# ZX_UNO_0_14.net
KiCad netlist of a schematic drawn in Altium Designer
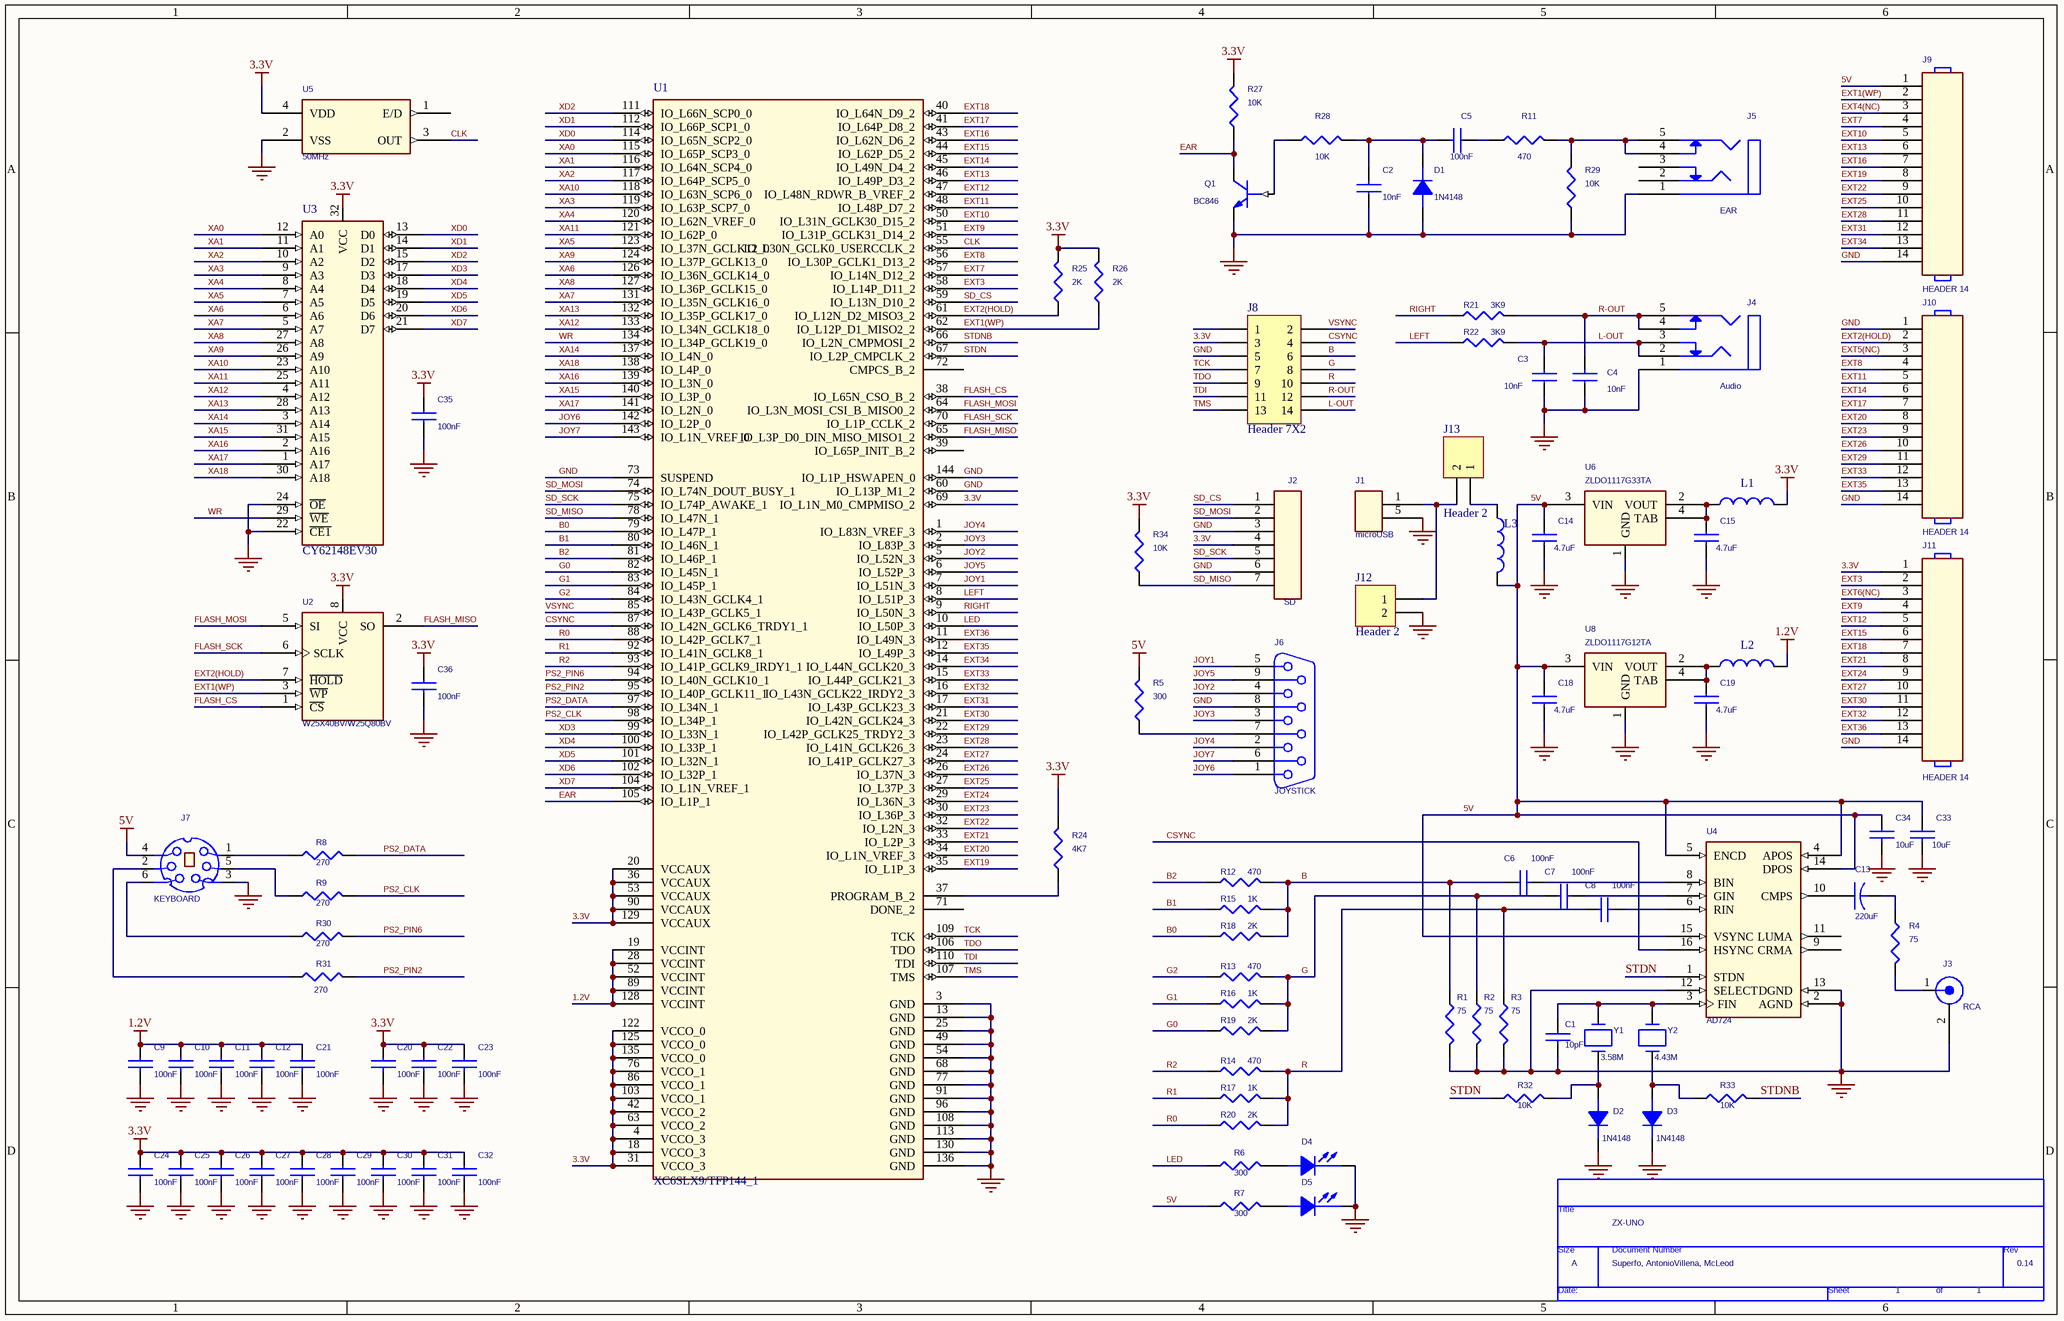
[diagram p0: ZX_UNO_0_14.SchDoc]

(export (version "E")
  (design (tool "Eeschema 10.0.6"))
  (components
    (comp (ref "*")
      (value "TitleBlock0")
      (fields
        (field (name "PAGE COUNT") "1")
        (field (name "PAGE NUMBER") "1")
        (field (name "PAGE SIZE") "A")
        (field (name "TITLE") "ZX-UNO")
        (field (name "REVCODE") "0.14")
        (field (name "DOC") "Superfo, AntonioVillena, McLeod")
      )
      (libsource (lib "*") (part "TitleBlock0"))
    )
    (comp (ref "C1") (value "10pF") (libsource (lib "*") (part "CAP NP_Dup1")))
    (comp (ref "C2") (value "10nF") (libsource (lib "*") (part "CAP NP_Dup1")))
    (comp (ref "C3") (value "10nF") (libsource (lib "*") (part "CAP NP_Dup1")))
    (comp (ref "C4") (value "10nF") (libsource (lib "*") (part "CAP NP_Dup1")))
    (comp (ref "C5") (value "100nF") (libsource (lib "*") (part "CAP NP_Dup1")))
    (comp (ref "C6") (value "100nF") (libsource (lib "*") (part "CAP NP_Dup1")))
    (comp (ref "C7") (value "100nF") (libsource (lib "*") (part "CAP NP_Dup1")))
    (comp (ref "C8") (value "100nF") (libsource (lib "*") (part "CAP NP_Dup1")))
    (comp (ref "C9") (value "100nF") (libsource (lib "*") (part "CAP NP")))
    (comp (ref "C10") (value "100nF") (libsource (lib "*") (part "CAP NP")))
    (comp (ref "C11") (value "100nF") (libsource (lib "*") (part "CAP NP")))
    (comp (ref "C12") (value "100nF") (libsource (lib "*") (part "CAP NP")))
    (comp (ref "C13") (value "220uF") (libsource (lib "*") (part "CAP")))
    (comp (ref "C14") (value "4.7uF") (libsource (lib "*") (part "CAP NP")))
    (comp (ref "C15") (value "4.7uF") (libsource (lib "*") (part "CAP NP")))
    (comp (ref "C18") (value "4.7uF") (libsource (lib "*") (part "CAP NP")))
    (comp (ref "C19") (value "4.7uF") (libsource (lib "*") (part "CAP NP")))
    (comp (ref "C20") (value "100nF") (libsource (lib "*") (part "CAP NP")))
    (comp (ref "C21") (value "100nF") (libsource (lib "*") (part "CAP NP")))
    (comp (ref "C22") (value "100nF") (libsource (lib "*") (part "CAP NP")))
    (comp (ref "C23") (value "100nF") (libsource (lib "*") (part "CAP NP")))
    (comp (ref "C24") (value "100nF") (libsource (lib "*") (part "CAP NP")))
    (comp (ref "C25") (value "100nF") (libsource (lib "*") (part "CAP NP")))
    (comp (ref "C26") (value "100nF") (libsource (lib "*") (part "CAP NP")))
    (comp (ref "C27") (value "100nF") (libsource (lib "*") (part "CAP NP")))
    (comp (ref "C28") (value "100nF") (libsource (lib "*") (part "CAP NP")))
    (comp (ref "C29") (value "100nF") (libsource (lib "*") (part "CAP NP")))
    (comp (ref "C30") (value "100nF") (libsource (lib "*") (part "CAP NP")))
    (comp (ref "C31") (value "100nF") (libsource (lib "*") (part "CAP NP")))
    (comp (ref "C32") (value "100nF") (libsource (lib "*") (part "CAP NP")))
    (comp (ref "C33") (value "10uF") (libsource (lib "*") (part "CAP NP")))
    (comp (ref "C34") (value "10uF") (libsource (lib "*") (part "CAP NP")))
    (comp (ref "C35") (value "100nF") (libsource (lib "*") (part "CAP NP")))
    (comp (ref "C36") (value "100nF") (libsource (lib "*") (part "CAP NP")))
    (comp (ref "D1") (value "1N4148") (libsource (lib "*") (part "DIODE")))
    (comp (ref "D2") (value "1N4148") (libsource (lib "*") (part "DIODE")))
    (comp (ref "D3") (value "1N4148") (libsource (lib "*") (part "DIODE")))
    (comp (ref "D4") (value "LED") (libsource (lib "*") (part "LED")))
    (comp (ref "D5") (value "LED") (libsource (lib "*") (part "LED")))
    (comp (ref "J1") (value "microUSB") (libsource (lib "*") (part "CON2_0")))
    (comp (ref "J2") (value "SD") (libsource (lib "*") (part "CON7")))
    (comp (ref "J3") (value "RCA") (libsource (lib "*") (part "RCA JACK")))
    (comp (ref "J4")
      (value "Audio")
      (footprint "AUDIO JACK STX-3120")
      (libsource (lib "*") (part "PHONEJACK STEREO SW_0"))
    )
    (comp (ref "J5") (value "EAR") (libsource (lib "*") (part "PHONEJACK STEREO SW_0")))
    (comp (ref "J6") (value "JOYSTICK") (libsource (lib "*") (part "CONNECTOR DB9")))
    (comp (ref "J7") (value "KEYBOARD") (libsource (lib "*") (part "M-DIN_0")))
    (comp (ref "J8")
      (value "Header 7X2")
      (footprint "HDR2X7")
      (description "Header, 7-Pin, Dual row")
      (fields (field (name "PUBLISHER") "Altium Limited"))
      (libsource (lib "Miscellaneous Connectors") (part "Header 7X2"))
    )
    (comp (ref "J9") (value "HEADER 14") (libsource (lib "*") (part "HEADER 14")))
    (comp (ref "J10") (value "HEADER 14") (libsource (lib "*") (part "HEADER 14")))
    (comp (ref "J11") (value "HEADER 14") (libsource (lib "*") (part "HEADER 14")))
    (comp (ref "J12")
      (value "Header 2")
      (footprint "HDR1X2")
      (description "Header, 2-Pin")
      (fields (field (name "PUBLISHER") "Altium Limited"))
      (libsource (lib "") (part "Header 2_1"))
    )
    (comp (ref "J13")
      (value "Header 2")
      (footprint "HDR1X2")
      (description "Header, 2-Pin")
      (fields (field (name "PUBLISHER") "Altium Limited"))
      (libsource (lib "Miscellaneous Connectors") (part "Header 2"))
    )
    (comp (ref "L1")
      (value "Inductor")
      (footprint "SM/L_0805")
      (fields (field (name "PUBLISHER") "Altium Limited"))
      (libsource (lib "Miscellaneous Devices") (part "Inductor"))
    )
    (comp (ref "L2")
      (value "Inductor")
      (footprint "SM/L_0805")
      (fields (field (name "PUBLISHER") "Altium Limited"))
      (libsource (lib "Miscellaneous Devices") (part "Inductor"))
    )
    (comp (ref "L3")
      (value "Inductor")
      (footprint "SM/L_0805")
      (fields (field (name "PUBLISHER") "Altium Limited"))
      (libsource (lib "Miscellaneous Devices") (part "Inductor"))
    )
    (comp (ref "Q1") (value "BC846") (libsource (lib "*") (part "BC547")))
    (comp (ref "R1") (value "75") (libsource (lib "*") (part "R")))
    (comp (ref "R2") (value "75") (libsource (lib "*") (part "R")))
    (comp (ref "R3") (value "75") (libsource (lib "*") (part "R")))
    (comp (ref "R4") (value "75") (libsource (lib "*") (part "R")))
    (comp (ref "R5") (value "300") (libsource (lib "*") (part "R")))
    (comp (ref "R6") (value "300") (libsource (lib "*") (part "R")))
    (comp (ref "R7") (value "300") (libsource (lib "*") (part "R")))
    (comp (ref "R8") (value "270") (libsource (lib "*") (part "R")))
    (comp (ref "R9") (value "270") (libsource (lib "*") (part "R")))
    (comp (ref "R11") (value "470") (libsource (lib "*") (part "R")))
    (comp (ref "R12") (value "470") (libsource (lib "*") (part "R")))
    (comp (ref "R13") (value "470") (libsource (lib "*") (part "R")))
    (comp (ref "R14") (value "470") (libsource (lib "*") (part "R")))
    (comp (ref "R15") (value "1K") (libsource (lib "*") (part "R")))
    (comp (ref "R16") (value "1K") (libsource (lib "*") (part "R")))
    (comp (ref "R17") (value "1K") (libsource (lib "*") (part "R")))
    (comp (ref "R18") (value "2K") (libsource (lib "*") (part "R")))
    (comp (ref "R19") (value "2K") (libsource (lib "*") (part "R")))
    (comp (ref "R20") (value "2K") (libsource (lib "*") (part "R")))
    (comp (ref "R21") (value "3K9") (libsource (lib "*") (part "R")))
    (comp (ref "R22") (value "3K9") (libsource (lib "*") (part "R")))
    (comp (ref "R24") (value "4K7") (libsource (lib "*") (part "R")))
    (comp (ref "R25") (value "2K") (libsource (lib "*") (part "R")))
    (comp (ref "R26") (value "2K") (libsource (lib "*") (part "R")))
    (comp (ref "R27") (value "10K") (libsource (lib "*") (part "R")))
    (comp (ref "R28") (value "10K") (libsource (lib "*") (part "R")))
    (comp (ref "R29") (value "10K") (libsource (lib "*") (part "R")))
    (comp (ref "R30") (value "270") (libsource (lib "*") (part "R")))
    (comp (ref "R31") (value "270") (libsource (lib "*") (part "R")))
    (comp (ref "R32") (value "10K") (libsource (lib "*") (part "R")))
    (comp (ref "R33") (value "10K") (libsource (lib "*") (part "R")))
    (comp (ref "R34") (value "10K") (libsource (lib "*") (part "R")))
    (comp (ref "U1")
      (value "XC6SLX9/TFP144_1")
      (libsource (lib "ZX_UNO_0_13_Library") (part "XC6SLX9/TFP144_1"))
    )
    (comp (ref "U2") (value "W25X40BV/W25Q80BV") (libsource (lib "*") (part "AT45DB011/SOIC_3")))
    (comp (ref "U3") (value "CY62148EV30") (libsource (lib "ZX_UNO_0_13_Library") (part "CY62128/SOIC_3")))
    (comp (ref "U4") (value "AD724") (libsource (lib "*") (part "AD724")))
    (comp (ref "U5") (value "50MHz") (libsource (lib "*") (part "CS-403/TO_0")))
    (comp (ref "U6")
      (value "ZLDO1117G33TA")
      (footprint "SM/SOT223")
      (libsource (lib "*") (part "REGULATOR-1_0"))
    )
    (comp (ref "U8")
      (value "ZLDO1117G12TA")
      (footprint "SM/SOT223")
      (libsource (lib "*") (part "REGULATOR-1_0"))
    )
    (comp (ref "Y1") (value "3.58M") (libsource (lib "*") (part "CRYSTAL")))
    (comp (ref "Y2") (value "4.43M") (libsource (lib "*") (part "CRYSTAL")))
  )
  (nets
    (net (code "1") (name "/B") (class "Default")
      (node (ref "C6") (pin "1") (pinfunction "1_1") (pintype "passive"))
      (node (ref "J8") (pin "6") (pinfunction "6_6") (pintype "passive"))
      (node (ref "R1") (pin "1") (pinfunction "1_1") (pintype "passive"))
      (node (ref "R12") (pin "2") (pinfunction "2_2") (pintype "passive"))
      (node (ref "R15") (pin "2") (pinfunction "2_2") (pintype "passive"))
      (node (ref "R18") (pin "2") (pinfunction "2_2") (pintype "passive"))
    )
    (net (code "2") (name "/B0") (class "Default")
      (node (ref "R18") (pin "1") (pinfunction "1_1") (pintype "passive"))
      (node (ref "U1") (pin "79") (pinfunction "IO_L47P_1_79") (pintype "bidirectional"))
    )
    (net (code "3") (name "/B1") (class "Default")
      (node (ref "R15") (pin "1") (pinfunction "1_1") (pintype "passive"))
      (node (ref "U1") (pin "80") (pinfunction "IO_L46N_1_80") (pintype "bidirectional"))
    )
    (net (code "4") (name "/B2") (class "Default")
      (node (ref "R12") (pin "1") (pinfunction "1_1") (pintype "passive"))
      (node (ref "U1") (pin "81") (pinfunction "IO_L46P_1_81") (pintype "bidirectional"))
    )
    (net (code "5") (name "/CLK") (class "Default")
      (node (ref "U1") (pin "55") (pinfunction "IO_L30N_GCLK0_USERCCLK_2_55") (pintype "bidirectional"))
      (node (ref "U5") (pin "3") (pinfunction "OUT_3") (pintype "output"))
    )
    (net (code "6") (name "/CSYNC") (class "Default")
      (node (ref "J8") (pin "4") (pinfunction "4_4") (pintype "passive"))
      (node (ref "U1") (pin "87") (pinfunction "IO_L42N_GCLK6_TRDY1_1_87") (pintype "bidirectional"))
      (node (ref "U4") (pin "16") (pinfunction "HSYNC_16") (pintype "input"))
    )
    (net (code "7") (name "/EAR") (class "Default")
      (node (ref "Q1") (pin "1") (pinfunction "COLLECTOR_1") (pintype "passive"))
      (node (ref "R27") (pin "2") (pinfunction "2_2") (pintype "passive"))
      (node (ref "U1") (pin "105") (pinfunction "IO_L1P_1_105") (pintype "bidirectional"))
    )
    (net (code "8") (name "/EXT1(WP)") (class "Default")
      (node (ref "J9") (pin "2") (pinfunction "2_2") (pintype "passive"))
      (node (ref "R26") (pin "1") (pinfunction "1_1") (pintype "passive"))
      (node (ref "U1") (pin "62") (pinfunction "IO_L12P_D1_MISO2_2_62") (pintype "bidirectional"))
      (node (ref "U2") (pin "3") (pinfunction "~{WP}_3") (pintype "input"))
    )
    (net (code "9") (name "/EXT2(HOLD)") (class "Default")
      (node (ref "J10") (pin "2") (pinfunction "2_2") (pintype "passive"))
      (node (ref "R25") (pin "1") (pinfunction "1_1") (pintype "passive"))
      (node (ref "U1") (pin "61") (pinfunction "IO_L12N_D2_MISO3_2_61") (pintype "bidirectional"))
      (node (ref "U2") (pin "7") (pinfunction "~{HOLD}_7") (pintype "input"))
    )
    (net (code "10") (name "/EXT3") (class "Default")
      (node (ref "J11") (pin "2") (pinfunction "2_2") (pintype "passive"))
      (node (ref "U1") (pin "58") (pinfunction "IO_L14P_D11_2_58") (pintype "bidirectional"))
    )
    (net (code "11") (name "/EXT4(NC)") (class "Default")
      (node (ref "J9") (pin "3") (pinfunction "3_3") (pintype "passive"))
    )
    (net (code "12") (name "/EXT5(NC)") (class "Default")
      (node (ref "J10") (pin "3") (pinfunction "3_3") (pintype "passive"))
    )
    (net (code "13") (name "/EXT6(NC)") (class "Default")
      (node (ref "J11") (pin "3") (pinfunction "3_3") (pintype "passive"))
    )
    (net (code "14") (name "/EXT7") (class "Default")
      (node (ref "J9") (pin "4") (pinfunction "4_4") (pintype "passive"))
      (node (ref "U1") (pin "57") (pinfunction "IO_L14N_D12_2_57") (pintype "bidirectional"))
    )
    (net (code "15") (name "/EXT8") (class "Default")
      (node (ref "J10") (pin "4") (pinfunction "4_4") (pintype "passive"))
      (node (ref "U1") (pin "56") (pinfunction "IO_L30P_GCLK1_D13_2_56") (pintype "bidirectional"))
    )
    (net (code "16") (name "/EXT9") (class "Default")
      (node (ref "J11") (pin "4") (pinfunction "4_4") (pintype "passive"))
      (node (ref "U1") (pin "51") (pinfunction "IO_L31P_GCLK31_D14_2_51") (pintype "bidirectional"))
    )
    (net (code "17") (name "/EXT10") (class "Default")
      (node (ref "J9") (pin "5") (pinfunction "5_5") (pintype "passive"))
      (node (ref "U1") (pin "50") (pinfunction "IO_L31N_GCLK30_D15_2_50") (pintype "bidirectional"))
    )
    (net (code "18") (name "/EXT11") (class "Default")
      (node (ref "J10") (pin "5") (pinfunction "5_5") (pintype "passive"))
      (node (ref "U1") (pin "48") (pinfunction "IO_L48P_D7_2_48") (pintype "bidirectional"))
    )
    (net (code "19") (name "/EXT12") (class "Default")
      (node (ref "J11") (pin "5") (pinfunction "5_5") (pintype "passive"))
      (node (ref "U1") (pin "47") (pinfunction "IO_L48N_RDWR_B_VREF_2_47") (pintype "bidirectional"))
    )
    (net (code "20") (name "/EXT13") (class "Default")
      (node (ref "J9") (pin "6") (pinfunction "6_6") (pintype "passive"))
      (node (ref "U1") (pin "46") (pinfunction "IO_L49P_D3_2_46") (pintype "bidirectional"))
    )
    (net (code "21") (name "/EXT14") (class "Default")
      (node (ref "J10") (pin "6") (pinfunction "6_6") (pintype "passive"))
      (node (ref "U1") (pin "45") (pinfunction "IO_L49N_D4_2_45") (pintype "bidirectional"))
    )
    (net (code "22") (name "/EXT15") (class "Default")
      (node (ref "J11") (pin "6") (pinfunction "6_6") (pintype "passive"))
      (node (ref "U1") (pin "44") (pinfunction "IO_L62P_D5_2_44") (pintype "bidirectional"))
    )
    (net (code "23") (name "/EXT16") (class "Default")
      (node (ref "J9") (pin "7") (pinfunction "7_7") (pintype "passive"))
      (node (ref "U1") (pin "43") (pinfunction "IO_L62N_D6_2_43") (pintype "bidirectional"))
    )
    (net (code "24") (name "/EXT17") (class "Default")
      (node (ref "J10") (pin "7") (pinfunction "7_7") (pintype "passive"))
      (node (ref "U1") (pin "41") (pinfunction "IO_L64P_D8_2_41") (pintype "bidirectional"))
    )
    (net (code "25") (name "/EXT18") (class "Default")
      (node (ref "J11") (pin "7") (pinfunction "7_7") (pintype "passive"))
      (node (ref "U1") (pin "40") (pinfunction "IO_L64N_D9_2_40") (pintype "bidirectional"))
    )
    (net (code "26") (name "/EXT19") (class "Default")
      (node (ref "J9") (pin "8") (pinfunction "8_8") (pintype "passive"))
      (node (ref "U1") (pin "35") (pinfunction "IO_L1P_3_35") (pintype "bidirectional"))
    )
    (net (code "27") (name "/EXT20") (class "Default")
      (node (ref "J10") (pin "8") (pinfunction "8_8") (pintype "passive"))
      (node (ref "U1") (pin "34") (pinfunction "IO_L1N_VREF_3_34") (pintype "bidirectional"))
    )
    (net (code "28") (name "/EXT21") (class "Default")
      (node (ref "J11") (pin "8") (pinfunction "8_8") (pintype "passive"))
      (node (ref "U1") (pin "33") (pinfunction "IO_L2P_3_33") (pintype "bidirectional"))
    )
    (net (code "29") (name "/EXT22") (class "Default")
      (node (ref "J9") (pin "9") (pinfunction "9_9") (pintype "passive"))
      (node (ref "U1") (pin "32") (pinfunction "IO_L2N_3_32") (pintype "bidirectional"))
    )
    (net (code "30") (name "/EXT23") (class "Default")
      (node (ref "J10") (pin "9") (pinfunction "9_9") (pintype "passive"))
      (node (ref "U1") (pin "30") (pinfunction "IO_L36P_3_30") (pintype "bidirectional"))
    )
    (net (code "31") (name "/EXT24") (class "Default")
      (node (ref "J11") (pin "9") (pinfunction "9_9") (pintype "passive"))
      (node (ref "U1") (pin "29") (pinfunction "IO_L36N_3_29") (pintype "bidirectional"))
    )
    (net (code "32") (name "/EXT25") (class "Default")
      (node (ref "J9") (pin "10") (pinfunction "10_10") (pintype "passive"))
      (node (ref "U1") (pin "27") (pinfunction "IO_L37P_3_27") (pintype "bidirectional"))
    )
    (net (code "33") (name "/EXT26") (class "Default")
      (node (ref "J10") (pin "10") (pinfunction "10_10") (pintype "passive"))
      (node (ref "U1") (pin "26") (pinfunction "IO_L37N_3_26") (pintype "bidirectional"))
    )
    (net (code "34") (name "/EXT27") (class "Default")
      (node (ref "J11") (pin "10") (pinfunction "10_10") (pintype "passive"))
      (node (ref "U1") (pin "24") (pinfunction "IO_L41P_GCLK27_3_24") (pintype "bidirectional"))
    )
    (net (code "35") (name "/EXT28") (class "Default")
      (node (ref "J9") (pin "11") (pinfunction "11_11") (pintype "passive"))
      (node (ref "U1") (pin "23") (pinfunction "IO_L41N_GCLK26_3_23") (pintype "bidirectional"))
    )
    (net (code "36") (name "/EXT29") (class "Default")
      (node (ref "J10") (pin "11") (pinfunction "11_11") (pintype "passive"))
      (node (ref "U1") (pin "22") (pinfunction "IO_L42P_GCLK25_TRDY2_3_22") (pintype "bidirectional"))
    )
    (net (code "37") (name "/EXT30") (class "Default")
      (node (ref "J11") (pin "11") (pinfunction "11_11") (pintype "passive"))
      (node (ref "U1") (pin "21") (pinfunction "IO_L42N_GCLK24_3_21") (pintype "bidirectional"))
    )
    (net (code "38") (name "/EXT31") (class "Default")
      (node (ref "J9") (pin "12") (pinfunction "12_12") (pintype "passive"))
      (node (ref "U1") (pin "17") (pinfunction "IO_L43P_GCLK23_3_17") (pintype "bidirectional"))
    )
    (net (code "39") (name "/EXT32") (class "Default")
      (node (ref "J11") (pin "12") (pinfunction "12_12") (pintype "passive"))
      (node (ref "U1") (pin "16") (pinfunction "IO_L43N_GCLK22_IRDY2_3_16") (pintype "bidirectional"))
    )
    (net (code "40") (name "/EXT33") (class "Default")
      (node (ref "J10") (pin "12") (pinfunction "12_12") (pintype "passive"))
      (node (ref "U1") (pin "15") (pinfunction "IO_L44P_GCLK21_3_15") (pintype "bidirectional"))
    )
    (net (code "41") (name "/EXT34") (class "Default")
      (node (ref "J9") (pin "13") (pinfunction "13_13") (pintype "passive"))
      (node (ref "U1") (pin "14") (pinfunction "IO_L44N_GCLK20_3_14") (pintype "bidirectional"))
    )
    (net (code "42") (name "/EXT35") (class "Default")
      (node (ref "J10") (pin "13") (pinfunction "13_13") (pintype "passive"))
      (node (ref "U1") (pin "12") (pinfunction "IO_L49P_3_12") (pintype "bidirectional"))
    )
    (net (code "43") (name "/EXT36") (class "Default")
      (node (ref "J11") (pin "13") (pinfunction "13_13") (pintype "passive"))
      (node (ref "U1") (pin "11") (pinfunction "IO_L49N_3_11") (pintype "bidirectional"))
    )
    (net (code "44") (name "/FLASH_CS") (class "Default")
      (node (ref "U1") (pin "38") (pinfunction "IO_L65N_CSO_B_2_38") (pintype "bidirectional"))
      (node (ref "U2") (pin "1") (pinfunction "~{CS}_1") (pintype "input"))
    )
    (net (code "45") (name "/FLASH_MISO") (class "Default")
      (node (ref "U1") (pin "65") (pinfunction "IO_L3P_D0_DIN_MISO_MISO1_2_65") (pintype "bidirectional"))
      (node (ref "U2") (pin "2") (pinfunction "SO_2") (pintype "tri_state"))
    )
    (net (code "46") (name "/FLASH_MOSI") (class "Default")
      (node (ref "U1") (pin "64") (pinfunction "IO_L3N_MOSI_CSI_B_MISO0_2_64") (pintype "bidirectional"))
      (node (ref "U2") (pin "5") (pinfunction "SI_5") (pintype "input"))
    )
    (net (code "47") (name "/FLASH_SCK") (class "Default")
      (node (ref "U1") (pin "70") (pinfunction "IO_L1P_CCLK_2_70") (pintype "bidirectional"))
      (node (ref "U2") (pin "6") (pinfunction "SCLK_6") (pintype "input"))
    )
    (net (code "48") (name "/G") (class "Default")
      (node (ref "C7") (pin "1") (pinfunction "1_1") (pintype "passive"))
      (node (ref "J8") (pin "8") (pinfunction "8_8") (pintype "passive"))
      (node (ref "R13") (pin "2") (pinfunction "2_2") (pintype "passive"))
      (node (ref "R16") (pin "2") (pinfunction "2_2") (pintype "passive"))
      (node (ref "R19") (pin "2") (pinfunction "2_2") (pintype "passive"))
      (node (ref "R2") (pin "1") (pinfunction "1_1") (pintype "passive"))
    )
    (net (code "49") (name "/G0") (class "Default")
      (node (ref "R19") (pin "1") (pinfunction "1_1") (pintype "passive"))
      (node (ref "U1") (pin "82") (pinfunction "IO_L45N_1_82") (pintype "bidirectional"))
    )
    (net (code "50") (name "/G1") (class "Default")
      (node (ref "R16") (pin "1") (pinfunction "1_1") (pintype "passive"))
      (node (ref "U1") (pin "83") (pinfunction "IO_L45P_1_83") (pintype "bidirectional"))
    )
    (net (code "51") (name "/G2") (class "Default")
      (node (ref "R13") (pin "1") (pinfunction "1_1") (pintype "passive"))
      (node (ref "U1") (pin "84") (pinfunction "IO_L43N_GCLK4_1_84") (pintype "bidirectional"))
    )
    (net (code "52") (name "/JOY1") (class "Default")
      (node (ref "J6") (pin "5") (pinfunction "5_5") (pintype "passive"))
      (node (ref "U1") (pin "7") (pinfunction "IO_L51N_3_7") (pintype "bidirectional"))
    )
    (net (code "53") (name "/JOY2") (class "Default")
      (node (ref "J6") (pin "4") (pinfunction "4_4") (pintype "passive"))
      (node (ref "U1") (pin "5") (pinfunction "IO_L52N_3_5") (pintype "bidirectional"))
    )
    (net (code "54") (name "/JOY3") (class "Default")
      (node (ref "J6") (pin "3") (pinfunction "3_3") (pintype "passive"))
      (node (ref "U1") (pin "2") (pinfunction "IO_L83P_3_2") (pintype "bidirectional"))
    )
    (net (code "55") (name "/JOY4") (class "Default")
      (node (ref "J6") (pin "2") (pinfunction "2_2") (pintype "passive"))
      (node (ref "U1") (pin "1") (pinfunction "IO_L83N_VREF_3_1") (pintype "bidirectional"))
    )
    (net (code "56") (name "/JOY5") (class "Default")
      (node (ref "J6") (pin "9") (pinfunction "9_9") (pintype "passive"))
      (node (ref "U1") (pin "6") (pinfunction "IO_L52P_3_6") (pintype "bidirectional"))
    )
    (net (code "57") (name "/JOY6") (class "Default")
      (node (ref "J6") (pin "1") (pinfunction "1_1") (pintype "passive"))
      (node (ref "U1") (pin "142") (pinfunction "IO_L2P_0_142") (pintype "bidirectional"))
    )
    (net (code "58") (name "/JOY7") (class "Default")
      (node (ref "J6") (pin "6") (pinfunction "6_6") (pintype "passive"))
      (node (ref "U1") (pin "143") (pinfunction "IO_L1N_VREF_0_143") (pintype "bidirectional"))
    )
    (net (code "59") (name "/L-OUT") (class "Default")
      (node (ref "C3") (pin "2") (pinfunction "2_2") (pintype "passive"))
      (node (ref "J4") (pin "2") (pinfunction "D_2") (pintype "passive"))
      (node (ref "J4") (pin "3") (pinfunction "C_3") (pintype "passive"))
      (node (ref "J8") (pin "14") (pinfunction "14_14") (pintype "passive"))
      (node (ref "R22") (pin "2") (pinfunction "2_2") (pintype "passive"))
    )
    (net (code "60") (name "/LED") (class "Default")
      (node (ref "R6") (pin "1") (pinfunction "1_1") (pintype "passive"))
      (node (ref "U1") (pin "10") (pinfunction "IO_L50P_3_10") (pintype "bidirectional"))
    )
    (net (code "61") (name "/LEFT") (class "Default")
      (node (ref "R22") (pin "1") (pinfunction "1_1") (pintype "passive"))
      (node (ref "U1") (pin "8") (pinfunction "IO_L51P_3_8") (pintype "bidirectional"))
    )
    (net (code "62") (name "/PS2_CLK") (class "Default")
      (node (ref "R9") (pin "2") (pinfunction "2_2") (pintype "passive"))
      (node (ref "U1") (pin "98") (pinfunction "IO_L34P_1_98") (pintype "bidirectional"))
    )
    (net (code "63") (name "/PS2_DATA") (class "Default")
      (node (ref "R8") (pin "2") (pinfunction "2_2") (pintype "passive"))
      (node (ref "U1") (pin "97") (pinfunction "IO_L34N_1_97") (pintype "bidirectional"))
    )
    (net (code "64") (name "/PS2_PIN2") (class "Default")
      (node (ref "R31") (pin "2") (pinfunction "2_2") (pintype "passive"))
      (node (ref "U1") (pin "95") (pinfunction "IO_L40P_GCLK11_1_95") (pintype "bidirectional"))
    )
    (net (code "65") (name "/PS2_PIN6") (class "Default")
      (node (ref "R30") (pin "2") (pinfunction "2_2") (pintype "passive"))
      (node (ref "U1") (pin "94") (pinfunction "IO_L40N_GCLK10_1_94") (pintype "bidirectional"))
    )
    (net (code "66") (name "/R") (class "Default")
      (node (ref "C8") (pin "1") (pinfunction "1_1") (pintype "passive"))
      (node (ref "J8") (pin "10") (pinfunction "10_10") (pintype "passive"))
      (node (ref "R14") (pin "2") (pinfunction "2_2") (pintype "passive"))
      (node (ref "R17") (pin "2") (pinfunction "2_2") (pintype "passive"))
      (node (ref "R20") (pin "2") (pinfunction "2_2") (pintype "passive"))
      (node (ref "R3") (pin "1") (pinfunction "1_1") (pintype "passive"))
    )
    (net (code "67") (name "/R-OUT") (class "Default")
      (node (ref "C4") (pin "2") (pinfunction "2_2") (pintype "passive"))
      (node (ref "J4") (pin "4") (pinfunction "B_4") (pintype "passive"))
      (node (ref "J4") (pin "5") (pinfunction "A_5") (pintype "passive"))
      (node (ref "J8") (pin "12") (pinfunction "12_12") (pintype "passive"))
      (node (ref "R21") (pin "2") (pinfunction "2_2") (pintype "passive"))
    )
    (net (code "68") (name "/R0") (class "Default")
      (node (ref "R20") (pin "1") (pinfunction "1_1") (pintype "passive"))
      (node (ref "U1") (pin "88") (pinfunction "IO_L42P_GCLK7_1_88") (pintype "bidirectional"))
    )
    (net (code "69") (name "/R1") (class "Default")
      (node (ref "R17") (pin "1") (pinfunction "1_1") (pintype "passive"))
      (node (ref "U1") (pin "92") (pinfunction "IO_L41N_GCLK8_1_92") (pintype "bidirectional"))
    )
    (net (code "70") (name "/R2") (class "Default")
      (node (ref "R14") (pin "1") (pinfunction "1_1") (pintype "passive"))
      (node (ref "U1") (pin "93") (pinfunction "IO_L41P_GCLK9_IRDY1_1_93") (pintype "bidirectional"))
    )
    (net (code "71") (name "/RIGHT") (class "Default")
      (node (ref "R21") (pin "1") (pinfunction "1_1") (pintype "passive"))
      (node (ref "U1") (pin "9") (pinfunction "IO_L50N_3_9") (pintype "bidirectional"))
    )
    (net (code "72") (name "/SD_CS") (class "Default")
      (node (ref "J2") (pin "1") (pinfunction "1_1") (pintype "passive"))
      (node (ref "U1") (pin "59") (pinfunction "IO_L13N_D10_2_59") (pintype "bidirectional"))
    )
    (net (code "73") (name "/SD_MISO") (class "Default")
      (node (ref "J2") (pin "7") (pinfunction "7_7") (pintype "passive"))
      (node (ref "R34") (pin "1") (pinfunction "1_1") (pintype "passive"))
      (node (ref "U1") (pin "78") (pinfunction "IO_L47N_1_78") (pintype "bidirectional"))
    )
    (net (code "74") (name "/SD_MOSI") (class "Default")
      (node (ref "J2") (pin "2") (pinfunction "2_2") (pintype "passive"))
      (node (ref "U1") (pin "74") (pinfunction "IO_L74N_DOUT_BUSY_1_74") (pintype "bidirectional"))
    )
    (net (code "75") (name "/SD_SCK") (class "Default")
      (node (ref "J2") (pin "5") (pinfunction "5_5") (pintype "passive"))
      (node (ref "U1") (pin "75") (pinfunction "IO_L74P_AWAKE_1_75") (pintype "bidirectional"))
    )
    (net (code "76") (name "/STDN") (class "Default")
      (node (ref "R32") (pin "1") (pinfunction "1_1") (pintype "passive"))
      (node (ref "U1") (pin "67") (pinfunction "IO_L2P_CMPCLK_2_67") (pintype "bidirectional"))
      (node (ref "U4") (pin "1") (pinfunction "STDN_1") (pintype "input"))
    )
    (net (code "77") (name "/STDNB") (class "Default")
      (node (ref "R33") (pin "2") (pinfunction "2_2") (pintype "passive"))
      (node (ref "U1") (pin "66") (pinfunction "IO_L2N_CMPMOSI_2_66") (pintype "bidirectional"))
    )
    (net (code "78") (name "/TCK") (class "Default")
      (node (ref "J8") (pin "7") (pinfunction "7_7") (pintype "passive"))
      (node (ref "U1") (pin "109") (pinfunction "TCK_109") (pintype "bidirectional"))
    )
    (net (code "79") (name "/TDI") (class "Default")
      (node (ref "J8") (pin "11") (pinfunction "11_11") (pintype "passive"))
      (node (ref "U1") (pin "110") (pinfunction "TDI_110") (pintype "bidirectional"))
    )
    (net (code "80") (name "/TDO") (class "Default")
      (node (ref "J8") (pin "9") (pinfunction "9_9") (pintype "passive"))
      (node (ref "U1") (pin "106") (pinfunction "TDO_106") (pintype "bidirectional"))
    )
    (net (code "81") (name "/TMS") (class "Default")
      (node (ref "J8") (pin "13") (pinfunction "13_13") (pintype "passive"))
      (node (ref "U1") (pin "107") (pinfunction "TMS_107") (pintype "bidirectional"))
    )
    (net (code "82") (name "/VSYNC") (class "Default")
      (node (ref "J8") (pin "2") (pinfunction "2_2") (pintype "passive"))
      (node (ref "U1") (pin "85") (pinfunction "IO_L43P_GCLK5_1_85") (pintype "bidirectional"))
    )
    (net (code "83") (name "/WR") (class "Default")
      (node (ref "U1") (pin "134") (pinfunction "IO_L34P_GCLK19_0_134") (pintype "bidirectional"))
      (node (ref "U3") (pin "29") (pinfunction "~{WE}_29") (pintype "input"))
    )
    (net (code "84") (name "/XA0") (class "Default")
      (node (ref "U1") (pin "115") (pinfunction "IO_L65P_SCP3_0_115") (pintype "bidirectional"))
      (node (ref "U3") (pin "12") (pinfunction "A0_12") (pintype "input"))
    )
    (net (code "85") (name "/XA1") (class "Default")
      (node (ref "U1") (pin "116") (pinfunction "IO_L64N_SCP4_0_116") (pintype "bidirectional"))
      (node (ref "U3") (pin "11") (pinfunction "A1_11") (pintype "input"))
    )
    (net (code "86") (name "/XA2") (class "Default")
      (node (ref "U1") (pin "117") (pinfunction "IO_L64P_SCP5_0_117") (pintype "bidirectional"))
      (node (ref "U3") (pin "10") (pinfunction "A2_10") (pintype "input"))
    )
    (net (code "87") (name "/XA3") (class "Default")
      (node (ref "U1") (pin "119") (pinfunction "IO_L63P_SCP7_0_119") (pintype "bidirectional"))
      (node (ref "U3") (pin "9") (pinfunction "A3_9") (pintype "input"))
    )
    (net (code "88") (name "/XA4") (class "Default")
      (node (ref "U1") (pin "120") (pinfunction "IO_L62N_VREF_0_120") (pintype "bidirectional"))
      (node (ref "U3") (pin "8") (pinfunction "A4_8") (pintype "input"))
    )
    (net (code "89") (name "/XA5") (class "Default")
      (node (ref "U1") (pin "123") (pinfunction "IO_L37N_GCLK12_0_123") (pintype "bidirectional"))
      (node (ref "U3") (pin "7") (pinfunction "A5_7") (pintype "input"))
    )
    (net (code "90") (name "/XA6") (class "Default")
      (node (ref "U1") (pin "126") (pinfunction "IO_L36N_GCLK14_0_126") (pintype "bidirectional"))
      (node (ref "U3") (pin "6") (pinfunction "A6_6") (pintype "input"))
    )
    (net (code "91") (name "/XA7") (class "Default")
      (node (ref "U1") (pin "131") (pinfunction "IO_L35N_GCLK16_0_131") (pintype "bidirectional"))
      (node (ref "U3") (pin "5") (pinfunction "A7_5") (pintype "input"))
    )
    (net (code "92") (name "/XA8") (class "Default")
      (node (ref "U1") (pin "127") (pinfunction "IO_L36P_GCLK15_0_127") (pintype "bidirectional"))
      (node (ref "U3") (pin "27") (pinfunction "A8_27") (pintype "input"))
    )
    (net (code "93") (name "/XA9") (class "Default")
      (node (ref "U1") (pin "124") (pinfunction "IO_L37P_GCLK13_0_124") (pintype "bidirectional"))
      (node (ref "U3") (pin "26") (pinfunction "A9_26") (pintype "input"))
    )
    (net (code "94") (name "/XA10") (class "Default")
      (node (ref "U1") (pin "118") (pinfunction "IO_L63N_SCP6_0_118") (pintype "bidirectional"))
      (node (ref "U3") (pin "23") (pinfunction "A10_23") (pintype "input"))
    )
    (net (code "95") (name "/XA11") (class "Default")
      (node (ref "U1") (pin "121") (pinfunction "IO_L62P_0_121") (pintype "bidirectional"))
      (node (ref "U3") (pin "25") (pinfunction "A11_25") (pintype "input"))
    )
    (net (code "96") (name "/XA12") (class "Default")
      (node (ref "U1") (pin "133") (pinfunction "IO_L34N_GCLK18_0_133") (pintype "bidirectional"))
      (node (ref "U3") (pin "4") (pinfunction "A12_4") (pintype "input"))
    )
    (net (code "97") (name "/XA13") (class "Default")
      (node (ref "U1") (pin "132") (pinfunction "IO_L35P_GCLK17_0_132") (pintype "bidirectional"))
      (node (ref "U3") (pin "28") (pinfunction "A13_28") (pintype "input"))
    )
    (net (code "98") (name "/XA14") (class "Default")
      (node (ref "U1") (pin "137") (pinfunction "IO_L4N_0_137") (pintype "bidirectional"))
      (node (ref "U3") (pin "3") (pinfunction "A14_3") (pintype "input"))
    )
    (net (code "99") (name "/XA15") (class "Default")
      (node (ref "U1") (pin "140") (pinfunction "IO_L3P_0_140") (pintype "bidirectional"))
      (node (ref "U3") (pin "31") (pinfunction "A15_31") (pintype "input"))
    )
    (net (code "100") (name "/XA16") (class "Default")
      (node (ref "U1") (pin "139") (pinfunction "IO_L3N_0_139") (pintype "bidirectional"))
      (node (ref "U3") (pin "2") (pinfunction "A16_2") (pintype "input"))
    )
    (net (code "101") (name "/XA17") (class "Default")
      (node (ref "U1") (pin "141") (pinfunction "IO_L2N_0_141") (pintype "bidirectional"))
      (node (ref "U3") (pin "1") (pinfunction "A17_1") (pintype "input"))
    )
    (net (code "102") (name "/XA18") (class "Default")
      (node (ref "U1") (pin "138") (pinfunction "IO_L4P_0_138") (pintype "bidirectional"))
      (node (ref "U3") (pin "30") (pinfunction "A18_30") (pintype "input"))
    )
    (net (code "103") (name "/XD0") (class "Default")
      (node (ref "U1") (pin "114") (pinfunction "IO_L65N_SCP2_0_114") (pintype "bidirectional"))
      (node (ref "U3") (pin "13") (pinfunction "D0_13") (pintype "bidirectional"))
    )
    (net (code "104") (name "/XD1") (class "Default")
      (node (ref "U1") (pin "112") (pinfunction "IO_L66P_SCP1_0_112") (pintype "bidirectional"))
      (node (ref "U3") (pin "14") (pinfunction "D1_14") (pintype "bidirectional"))
    )
    (net (code "105") (name "/XD2") (class "Default")
      (node (ref "U1") (pin "111") (pinfunction "IO_L66N_SCP0_0_111") (pintype "bidirectional"))
      (node (ref "U3") (pin "15") (pinfunction "D2_15") (pintype "bidirectional"))
    )
    (net (code "106") (name "/XD3") (class "Default")
      (node (ref "U1") (pin "99") (pinfunction "IO_L33N_1_99") (pintype "bidirectional"))
      (node (ref "U3") (pin "17") (pinfunction "D3_17") (pintype "bidirectional"))
    )
    (net (code "107") (name "/XD4") (class "Default")
      (node (ref "U1") (pin "100") (pinfunction "IO_L33P_1_100") (pintype "bidirectional"))
      (node (ref "U3") (pin "18") (pinfunction "D4_18") (pintype "bidirectional"))
    )
    (net (code "108") (name "/XD5") (class "Default")
      (node (ref "U1") (pin "101") (pinfunction "IO_L32N_1_101") (pintype "bidirectional"))
      (node (ref "U3") (pin "19") (pinfunction "D5_19") (pintype "bidirectional"))
    )
    (net (code "109") (name "/XD6") (class "Default")
      (node (ref "U1") (pin "102") (pinfunction "IO_L32P_1_102") (pintype "bidirectional"))
      (node (ref "U3") (pin "20") (pinfunction "D6_20") (pintype "bidirectional"))
    )
    (net (code "110") (name "/XD7") (class "Default")
      (node (ref "U1") (pin "104") (pinfunction "IO_L1N_VREF_1_104") (pintype "bidirectional"))
      (node (ref "U3") (pin "21") (pinfunction "D7_21") (pintype "bidirectional"))
    )
    (net (code "111") (name "1.2V") (class "Default")
      (node (ref "C10") (pin "1") (pinfunction "1_1") (pintype "passive"))
      (node (ref "C11") (pin "1") (pinfunction "1_1") (pintype "passive"))
      (node (ref "C12") (pin "1") (pinfunction "1_1") (pintype "passive"))
      (node (ref "C21") (pin "1") (pinfunction "1_1") (pintype "passive"))
      (node (ref "C9") (pin "1") (pinfunction "1_1") (pintype "passive"))
      (node (ref "L2") (pin "2") (pinfunction "2_2") (pintype "passive"))
      (node (ref "U1") (pin "128") (pinfunction "VCCINT_128") (pintype "passive"))
      (node (ref "U1") (pin "19") (pinfunction "VCCINT_19") (pintype "passive"))
      (node (ref "U1") (pin "28") (pinfunction "VCCINT_28") (pintype "passive"))
      (node (ref "U1") (pin "52") (pinfunction "VCCINT_52") (pintype "passive"))
      (node (ref "U1") (pin "89") (pinfunction "VCCINT_89") (pintype "passive"))
    )
    (net (code "112") (name "3.3V") (class "Default")
      (node (ref "C20") (pin "1") (pinfunction "1_1") (pintype "passive"))
      (node (ref "C22") (pin "1") (pinfunction "1_1") (pintype "passive"))
      (node (ref "C23") (pin "1") (pinfunction "1_1") (pintype "passive"))
      (node (ref "C24") (pin "1") (pinfunction "1_1") (pintype "passive"))
      (node (ref "C25") (pin "1") (pinfunction "1_1") (pintype "passive"))
      (node (ref "C26") (pin "1") (pinfunction "1_1") (pintype "passive"))
      (node (ref "C27") (pin "1") (pinfunction "1_1") (pintype "passive"))
      (node (ref "C28") (pin "1") (pinfunction "1_1") (pintype "passive"))
      (node (ref "C29") (pin "1") (pinfunction "1_1") (pintype "passive"))
      (node (ref "C30") (pin "1") (pinfunction "1_1") (pintype "passive"))
      (node (ref "C31") (pin "1") (pinfunction "1_1") (pintype "passive"))
      (node (ref "C32") (pin "1") (pinfunction "1_1") (pintype "passive"))
      (node (ref "C35") (pin "1") (pinfunction "1_1") (pintype "passive"))
      (node (ref "C36") (pin "1") (pinfunction "1_1") (pintype "passive"))
      (node (ref "J11") (pin "1") (pinfunction "1_1") (pintype "passive"))
      (node (ref "J2") (pin "4") (pinfunction "4_4") (pintype "passive"))
      (node (ref "J8") (pin "3") (pinfunction "3_3") (pintype "passive"))
      (node (ref "L1") (pin "2") (pinfunction "2_2") (pintype "passive"))
      (node (ref "R24") (pin "2") (pinfunction "2_2") (pintype "passive"))
      (node (ref "R25") (pin "2") (pinfunction "2_2") (pintype "passive"))
      (node (ref "R26") (pin "2") (pinfunction "2_2") (pintype "passive"))
      (node (ref "R27") (pin "1") (pinfunction "1_1") (pintype "passive"))
      (node (ref "R34") (pin "2") (pinfunction "2_2") (pintype "passive"))
      (node (ref "U1") (pin "103") (pinfunction "VCCO_1_103") (pintype "passive"))
      (node (ref "U1") (pin "122") (pinfunction "VCCO_0_122") (pintype "passive"))
      (node (ref "U1") (pin "125") (pinfunction "VCCO_0_125") (pintype "passive"))
      (node (ref "U1") (pin "129") (pinfunction "VCCAUX_129") (pintype "passive"))
      (node (ref "U1") (pin "135") (pinfunction "VCCO_0_135") (pintype "passive"))
      (node (ref "U1") (pin "18") (pinfunction "VCCO_3_18") (pintype "passive"))
      (node (ref "U1") (pin "20") (pinfunction "VCCAUX_20") (pintype "passive"))
      (node (ref "U1") (pin "31") (pinfunction "VCCO_3_31") (pintype "passive"))
      (node (ref "U1") (pin "36") (pinfunction "VCCAUX_36") (pintype "passive"))
      (node (ref "U1") (pin "4") (pinfunction "VCCO_3_4") (pintype "passive"))
      (node (ref "U1") (pin "42") (pinfunction "VCCO_2_42") (pintype "passive"))
      (node (ref "U1") (pin "53") (pinfunction "VCCAUX_53") (pintype "passive"))
      (node (ref "U1") (pin "63") (pinfunction "VCCO_2_63") (pintype "passive"))
      (node (ref "U1") (pin "69") (pinfunction "IO_L1N_M0_CMPMISO_2_69") (pintype "bidirectional"))
      (node (ref "U1") (pin "76") (pinfunction "VCCO_1_76") (pintype "passive"))
      (node (ref "U1") (pin "86") (pinfunction "VCCO_1_86") (pintype "passive"))
      (node (ref "U1") (pin "90") (pinfunction "VCCAUX_90") (pintype "passive"))
      (node (ref "U2") (pin "8") (pinfunction "VCC_8") (pintype "power_in"))
      (node (ref "U3") (pin "32") (pinfunction "VCC_32") (pintype "power_in"))
      (node (ref "U5") (pin "4") (pinfunction "VDD_4") (pintype "power_in"))
    )
    (net (code "113") (name "5V") (class "Default")
      (node (ref "C14") (pin "1") (pinfunction "1_1") (pintype "passive"))
      (node (ref "C18") (pin "1") (pinfunction "1_1") (pintype "passive"))
      (node (ref "C33") (pin "1") (pinfunction "1_1") (pintype "passive"))
      (node (ref "C34") (pin "1") (pinfunction "1_1") (pintype "passive"))
      (node (ref "J7") (pin "4") (pinfunction "4_4") (pintype "passive"))
      (node (ref "J9") (pin "1") (pinfunction "1_1") (pintype "passive"))
      (node (ref "L3") (pin "2") (pinfunction "2_2") (pintype "passive"))
      (node (ref "R5") (pin "2") (pinfunction "2_2") (pintype "passive"))
      (node (ref "R7") (pin "1") (pinfunction "1_1") (pintype "passive"))
      (node (ref "U4") (pin "14") (pinfunction "DPOS_14") (pintype "input"))
      (node (ref "U4") (pin "15") (pinfunction "VSYNC_15") (pintype "input"))
      (node (ref "U4") (pin "4") (pinfunction "APOS_4") (pintype "input"))
      (node (ref "U4") (pin "5") (pinfunction "ENCD_5") (pintype "input"))
      (node (ref "U6") (pin "3") (pinfunction "VIN_3") (pintype "power_in"))
      (node (ref "U8") (pin "3") (pinfunction "VIN_3") (pintype "power_in"))
    )
    (net (code "114") (name "GND") (class "Default")
      (node (ref "C1") (pin "2") (pinfunction "2_2") (pintype "passive"))
      (node (ref "C10") (pin "2") (pinfunction "2_2") (pintype "passive"))
      (node (ref "C11") (pin "2") (pinfunction "2_2") (pintype "passive"))
      (node (ref "C12") (pin "2") (pinfunction "2_2") (pintype "passive"))
      (node (ref "C14") (pin "2") (pinfunction "2_2") (pintype "passive"))
      (node (ref "C15") (pin "2") (pinfunction "2_2") (pintype "passive"))
      (node (ref "C18") (pin "2") (pinfunction "2_2") (pintype "passive"))
      (node (ref "C19") (pin "2") (pinfunction "2_2") (pintype "passive"))
      (node (ref "C2") (pin "1") (pinfunction "1_1") (pintype "passive"))
      (node (ref "C20") (pin "2") (pinfunction "2_2") (pintype "passive"))
      (node (ref "C21") (pin "2") (pinfunction "2_2") (pintype "passive"))
      (node (ref "C22") (pin "2") (pinfunction "2_2") (pintype "passive"))
      (node (ref "C23") (pin "2") (pinfunction "2_2") (pintype "passive"))
      (node (ref "C24") (pin "2") (pinfunction "2_2") (pintype "passive"))
      (node (ref "C25") (pin "2") (pinfunction "2_2") (pintype "passive"))
      (node (ref "C26") (pin "2") (pinfunction "2_2") (pintype "passive"))
      (node (ref "C27") (pin "2") (pinfunction "2_2") (pintype "passive"))
      (node (ref "C28") (pin "2") (pinfunction "2_2") (pintype "passive"))
      (node (ref "C29") (pin "2") (pinfunction "2_2") (pintype "passive"))
      (node (ref "C3") (pin "1") (pinfunction "1_1") (pintype "passive"))
      (node (ref "C30") (pin "2") (pinfunction "2_2") (pintype "passive"))
      (node (ref "C31") (pin "2") (pinfunction "2_2") (pintype "passive"))
      (node (ref "C32") (pin "2") (pinfunction "2_2") (pintype "passive"))
      (node (ref "C33") (pin "2") (pinfunction "2_2") (pintype "passive"))
      (node (ref "C34") (pin "2") (pinfunction "2_2") (pintype "passive"))
      (node (ref "C35") (pin "2") (pinfunction "2_2") (pintype "passive"))
      (node (ref "C36") (pin "2") (pinfunction "2_2") (pintype "passive"))
      (node (ref "C4") (pin "1") (pinfunction "1_1") (pintype "passive"))
      (node (ref "C9") (pin "2") (pinfunction "2_2") (pintype "passive"))
      (node (ref "D1") (pin "1") (pinfunction "A_1") (pintype "passive"))
      (node (ref "D2") (pin "2") (pinfunction "K_2") (pintype "passive"))
      (node (ref "D3") (pin "2") (pinfunction "K_2") (pintype "passive"))
      (node (ref "D4") (pin "2") (pinfunction "CATHODE_2") (pintype "passive"))
      (node (ref "D5") (pin "2") (pinfunction "CATHODE_2") (pintype "passive"))
      (node (ref "J1") (pin "5") (pinfunction "5_5") (pintype "passive"))
      (node (ref "J10") (pin "1") (pinfunction "1_1") (pintype "passive"))
      (node (ref "J10") (pin "14") (pinfunction "14_14") (pintype "passive"))
      (node (ref "J11") (pin "14") (pinfunction "14_14") (pintype "passive"))
      (node (ref "J12") (pin "2") (pinfunction "2_2") (pintype "passive"))
      (node (ref "J2") (pin "3") (pinfunction "3_3") (pintype "passive"))
      (node (ref "J2") (pin "6") (pinfunction "6_6") (pintype "passive"))
      (node (ref "J3") (pin "2") (pinfunction "SHIELD_2") (pintype "passive"))
      (node (ref "J4") (pin "1") (pinfunction "E_1") (pintype "passive"))
      (node (ref "J5") (pin "1") (pinfunction "E_1") (pintype "passive"))
      (node (ref "J6") (pin "8") (pinfunction "8_8") (pintype "passive"))
      (node (ref "J7") (pin "3") (pinfunction "3_3") (pintype "passive"))
      (node (ref "J7") (pin "M1") (pinfunction "GND_M1") (pintype "power_in"))
      (node (ref "J7") (pin "M2") (pinfunction "GND_M2") (pintype "power_in"))
      (node (ref "J7") (pin "M3") (pinfunction "GND_M3") (pintype "power_in"))
      (node (ref "J8") (pin "5") (pinfunction "5_5") (pintype "passive"))
      (node (ref "J9") (pin "14") (pinfunction "14_14") (pintype "passive"))
      (node (ref "Q1") (pin "3") (pinfunction "EMITTER_3") (pintype "passive"))
      (node (ref "R1") (pin "2") (pinfunction "2_2") (pintype "passive"))
      (node (ref "R2") (pin "2") (pinfunction "2_2") (pintype "passive"))
      (node (ref "R29") (pin "2") (pinfunction "2_2") (pintype "passive"))
      (node (ref "R3") (pin "2") (pinfunction "2_2") (pintype "passive"))
      (node (ref "U1") (pin "108") (pinfunction "GND_108") (pintype "power_in"))
      (node (ref "U1") (pin "113") (pinfunction "GND_113") (pintype "power_in"))
      (node (ref "U1") (pin "13") (pinfunction "GND_13") (pintype "passive"))
      (node (ref "U1") (pin "130") (pinfunction "GND_130") (pintype "passive"))
      (node (ref "U1") (pin "136") (pinfunction "GND_136") (pintype "passive"))
      (node (ref "U1") (pin "144") (pinfunction "IO_L1P_HSWAPEN_0_144") (pintype "bidirectional"))
      (node (ref "U1") (pin "25") (pinfunction "GND_25") (pintype "passive"))
      (node (ref "U1") (pin "3") (pinfunction "GND_3") (pintype "passive"))
      (node (ref "U1") (pin "49") (pinfunction "GND_49") (pintype "passive"))
      (node (ref "U1") (pin "54") (pinfunction "GND_54") (pintype "passive"))
      (node (ref "U1") (pin "60") (pinfunction "IO_L13P_M1_2_60") (pintype "bidirectional"))
      (node (ref "U1") (pin "68") (pinfunction "GND_68") (pintype "passive"))
      (node (ref "U1") (pin "73") (pinfunction "SUSPEND_73") (pintype "passive"))
      (node (ref "U1") (pin "77") (pinfunction "GND_77") (pintype "power_in"))
      (node (ref "U1") (pin "91") (pinfunction "GND_91") (pintype "power_in"))
      (node (ref "U1") (pin "96") (pinfunction "GND_96") (pintype "power_in"))
      (node (ref "U2") (pin "4") (pinfunction "GND_4") (pintype "power_in"))
      (node (ref "U3") (pin "16") (pinfunction "GND_16") (pintype "power_in"))
      (node (ref "U3") (pin "22") (pinfunction "~{CE1}_22") (pintype "input"))
      (node (ref "U3") (pin "24") (pinfunction "~{OE}_24") (pintype "input"))
      (node (ref "U4") (pin "12") (pinfunction "SELECT_12") (pintype "input"))
      (node (ref "U4") (pin "13") (pinfunction "DGND_13") (pintype "input"))
      (node (ref "U4") (pin "2") (pinfunction "AGND_2") (pintype "input"))
      (node (ref "U5") (pin "2") (pinfunction "VSS_2") (pintype "passive"))
      (node (ref "U6") (pin "1") (pinfunction "GND_1") (pintype "power_in"))
      (node (ref "U8") (pin "1") (pinfunction "GND_1") (pintype "power_in"))
    )
    (net (code "115") (name "Net-(C5-Pad1)") (class "Default")
      (node (ref "C5") (pin "1") (pinfunction "1_1") (pintype "passive"))
      (node (ref "R11") (pin "2") (pinfunction "2_2") (pintype "passive"))
    )
    (net (code "116") (name "Net-(C13-Pad2)") (class "Default")
      (node (ref "C13") (pin "2") (pinfunction "2_2") (pintype "passive"))
      (node (ref "R4") (pin "1") (pinfunction "1_1") (pintype "passive"))
    )
    (net (code "117") (name "Net-(D1-K)") (class "Default")
      (node (ref "C2") (pin "2") (pinfunction "2_2") (pintype "passive"))
      (node (ref "C5") (pin "2") (pinfunction "2_2") (pintype "passive"))
      (node (ref "D1") (pin "2") (pinfunction "K_2") (pintype "passive"))
      (node (ref "R28") (pin "1") (pinfunction "1_1") (pintype "passive"))
    )
    (net (code "118") (name "Net-(D2-A)") (class "Default")
      (node (ref "D2") (pin "1") (pinfunction "A_1") (pintype "passive"))
      (node (ref "R32") (pin "2") (pinfunction "2_2") (pintype "passive"))
      (node (ref "Y1") (pin "2") (pinfunction "2_2") (pintype "passive"))
    )
    (net (code "119") (name "Net-(D3-A)") (class "Default")
      (node (ref "D3") (pin "1") (pinfunction "A_1") (pintype "passive"))
      (node (ref "R33") (pin "1") (pinfunction "1_1") (pintype "passive"))
      (node (ref "Y2") (pin "2") (pinfunction "2_2") (pintype "passive"))
    )
    (net (code "120") (name "Net-(D4-ANODE)") (class "Default")
      (node (ref "D4") (pin "1") (pinfunction "ANODE_1") (pintype "passive"))
      (node (ref "R6") (pin "2") (pinfunction "2_2") (pintype "passive"))
    )
    (net (code "121") (name "Net-(D5-ANODE)") (class "Default")
      (node (ref "D5") (pin "1") (pinfunction "ANODE_1") (pintype "passive"))
      (node (ref "R7") (pin "2") (pinfunction "2_2") (pintype "passive"))
    )
    (net (code "122") (name "Net-(J1-Pad1)") (class "Default")
      (node (ref "J1") (pin "1") (pinfunction "1_1") (pintype "passive"))
      (node (ref "J12") (pin "1") (pinfunction "1_1") (pintype "passive"))
      (node (ref "J13") (pin "2") (pinfunction "2_2") (pintype "passive"))
    )
    (net (code "123") (name "Net-(J3-CENTER)") (class "Default")
      (node (ref "J3") (pin "1") (pinfunction "CENTER_1") (pintype "passive"))
      (node (ref "R4") (pin "2") (pinfunction "2_2") (pintype "passive"))
    )
    (net (code "124") (name "Net-(J5-A)") (class "Default")
      (node (ref "J5") (pin "4") (pinfunction "B_4") (pintype "passive"))
      (node (ref "J5") (pin "5") (pinfunction "A_5") (pintype "passive"))
      (node (ref "R11") (pin "1") (pinfunction "1_1") (pintype "passive"))
      (node (ref "R29") (pin "1") (pinfunction "1_1") (pintype "passive"))
    )
    (net (code "125") (name "Net-(J6-Pad7)") (class "Default")
      (node (ref "J6") (pin "7") (pinfunction "7_7") (pintype "passive"))
      (node (ref "R5") (pin "1") (pinfunction "1_1") (pintype "passive"))
    )
    (net (code "126") (name "Net-(J7-Pad1)") (class "Default")
      (node (ref "J7") (pin "1") (pinfunction "1_1") (pintype "passive"))
      (node (ref "R8") (pin "1") (pinfunction "1_1") (pintype "passive"))
    )
    (net (code "127") (name "Net-(J7-Pad2)") (class "Default")
      (node (ref "J7") (pin "2") (pinfunction "2_2") (pintype "passive"))
      (node (ref "R31") (pin "1") (pinfunction "1_1") (pintype "passive"))
    )
    (net (code "128") (name "Net-(J7-Pad5)") (class "Default")
      (node (ref "J7") (pin "5") (pinfunction "5_5") (pintype "passive"))
      (node (ref "R9") (pin "1") (pinfunction "1_1") (pintype "passive"))
    )
    (net (code "129") (name "Net-(J7-Pad6)") (class "Default")
      (node (ref "J7") (pin "6") (pinfunction "6_6") (pintype "passive"))
      (node (ref "R30") (pin "1") (pinfunction "1_1") (pintype "passive"))
    )
    (net (code "130") (name "Net-(J13-Pad1)") (class "Default")
      (node (ref "J13") (pin "1") (pinfunction "1_1") (pintype "passive"))
      (node (ref "L3") (pin "1") (pinfunction "1_1") (pintype "passive"))
    )
    (net (code "131") (name "Net-(Q1-BASE)") (class "Default")
      (node (ref "Q1") (pin "2") (pinfunction "BASE_2") (pintype "input"))
      (node (ref "R28") (pin "2") (pinfunction "2_2") (pintype "passive"))
    )
    (net (code "132") (name "Net-(U1-PROGRAM_B_2)") (class "Default")
      (node (ref "R24") (pin "1") (pinfunction "1_1") (pintype "passive"))
      (node (ref "U1") (pin "37") (pinfunction "PROGRAM_B_2_37") (pintype "passive"))
    )
    (net (code "133") (name "Net-(U4-BIN)") (class "Default")
      (node (ref "C6") (pin "2") (pinfunction "2_2") (pintype "passive"))
      (node (ref "U4") (pin "8") (pinfunction "BIN_8") (pintype "input"))
    )
    (net (code "134") (name "Net-(U4-CMPS)") (class "Default")
      (node (ref "C13") (pin "1") (pinfunction "1_1") (pintype "passive"))
      (node (ref "U4") (pin "10") (pinfunction "CMPS_10") (pintype "output"))
    )
    (net (code "135") (name "Net-(U4-FIN)") (class "Default")
      (node (ref "C1") (pin "1") (pinfunction "1_1") (pintype "passive"))
      (node (ref "U4") (pin "3") (pinfunction "FIN_3") (pintype "input"))
      (node (ref "Y1") (pin "1") (pinfunction "1_1") (pintype "passive"))
      (node (ref "Y2") (pin "1") (pinfunction "1_1") (pintype "passive"))
    )
    (net (code "136") (name "Net-(U4-GIN)") (class "Default")
      (node (ref "C7") (pin "2") (pinfunction "2_2") (pintype "passive"))
      (node (ref "U4") (pin "7") (pinfunction "GIN_7") (pintype "input"))
    )
    (net (code "137") (name "Net-(U4-RIN)") (class "Default")
      (node (ref "C8") (pin "2") (pinfunction "2_2") (pintype "passive"))
      (node (ref "U4") (pin "6") (pinfunction "RIN_6") (pintype "input"))
    )
    (net (code "138") (name "Net-(U6-TAB)") (class "Default")
      (node (ref "C15") (pin "1") (pinfunction "1_1") (pintype "passive"))
      (node (ref "L1") (pin "1") (pinfunction "1_1") (pintype "passive"))
      (node (ref "U6") (pin "2") (pinfunction "VOUT_2") (pintype "power_in"))
      (node (ref "U6") (pin "4") (pinfunction "TAB_4") (pintype "passive"))
    )
    (net (code "139") (name "Net-(U8-TAB)") (class "Default")
      (node (ref "C19") (pin "1") (pinfunction "1_1") (pintype "passive"))
      (node (ref "L2") (pin "1") (pinfunction "1_1") (pintype "passive"))
      (node (ref "U8") (pin "2") (pinfunction "VOUT_2") (pintype "power_in"))
      (node (ref "U8") (pin "4") (pinfunction "TAB_4") (pintype "passive"))
    )
    (net (code "140") (name "unconnected-(J5-C-Pad3)") (class "Default")
      (node (ref "J5") (pin "3") (pinfunction "C_3") (pintype "passive"))
    )
    (net (code "141") (name "unconnected-(J5-D-Pad2)") (class "Default")
      (node (ref "J5") (pin "2") (pinfunction "D_2") (pintype "passive"))
    )
    (net (code "142") (name "unconnected-(J8-Pad1)") (class "Default")
      (node (ref "J8") (pin "1") (pinfunction "1_1") (pintype "passive"))
    )
    (net (code "143") (name "unconnected-(U1-CMPCS_B_2-Pad72)") (class "Default")
      (node (ref "U1") (pin "72") (pinfunction "CMPCS_B_2_72") (pintype "passive"))
    )
    (net (code "144") (name "unconnected-(U1-DONE_2-Pad71)") (class "Default")
      (node (ref "U1") (pin "71") (pinfunction "DONE_2_71") (pintype "passive"))
    )
    (net (code "145") (name "unconnected-(U1-IO_L65P_INIT_B_2-Pad39)") (class "Default")
      (node (ref "U1") (pin "39") (pinfunction "IO_L65P_INIT_B_2_39") (pintype "bidirectional"))
    )
    (net (code "146") (name "unconnected-(U4-CRMA-Pad9)") (class "Default")
      (node (ref "U4") (pin "9") (pinfunction "CRMA_9") (pintype "output"))
    )
    (net (code "147") (name "unconnected-(U4-LUMA-Pad11)") (class "Default")
      (node (ref "U4") (pin "11") (pinfunction "LUMA_11") (pintype "output"))
    )
    (net (code "148") (name "unconnected-(U5-E{slash}D-Pad1)") (class "Default")
      (node (ref "U5") (pin "1") (pinfunction "E/D_1") (pintype "output"))
    )
  )
)
